# lan_board.net
KiCad netlist of a schematic drawn in Altium Designer
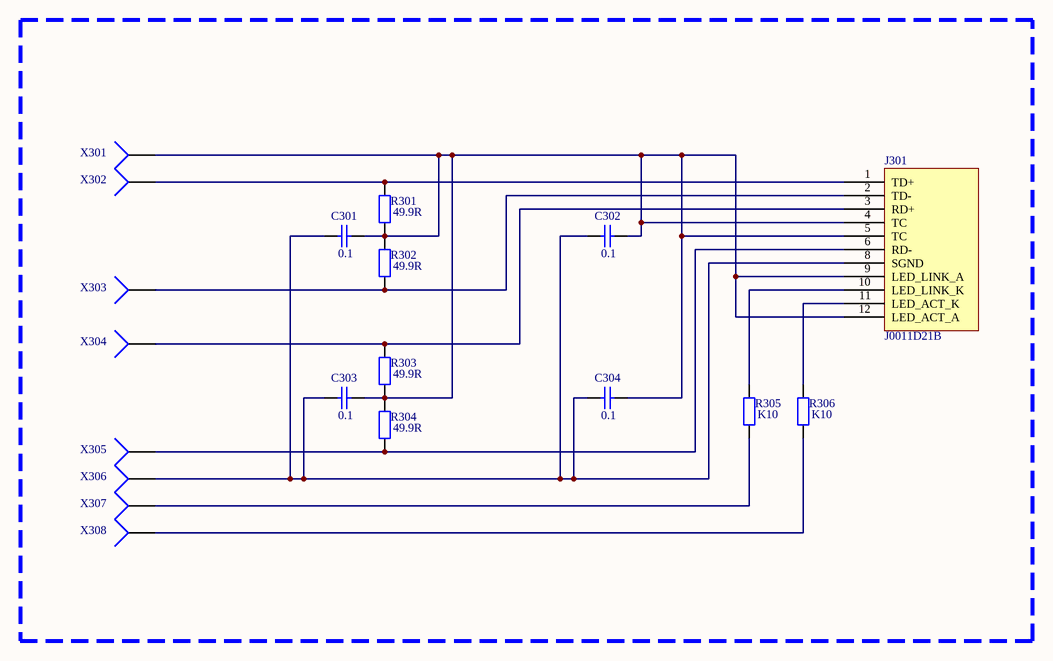
[diagram p0: lan_board.SchDoc]

(export (version "E")
  (design (tool "Eeschema 10.0.6"))
  (components
    (comp (ref "C301")
      (value "0.1")
      (footprint "C3216-1206")
      (description "Capacitor (Semiconductor SIM Model)")
      (fields (field (name "MANUFACTURER") "Generic Components") (field (name "PUBLISHER") "Altium Limited"))
      (libsource (lib "Miscellaneous Devices") (part "Cap Semi"))
    )
    (comp (ref "C302")
      (value "0.1")
      (footprint "C3216-1206")
      (description "Capacitor (Semiconductor SIM Model)")
      (fields (field (name "MANUFACTURER") "Generic Components") (field (name "PUBLISHER") "Altium Limited"))
      (libsource (lib "Miscellaneous Devices") (part "Cap Semi"))
    )
    (comp (ref "C303")
      (value "0.1")
      (footprint "C3216-1206")
      (description "Capacitor (Semiconductor SIM Model)")
      (fields (field (name "MANUFACTURER") "Generic Components") (field (name "PUBLISHER") "Altium Limited"))
      (libsource (lib "Miscellaneous Devices") (part "Cap Semi"))
    )
    (comp (ref "C304")
      (value "0.1")
      (footprint "C3216-1206")
      (description "Capacitor (Semiconductor SIM Model)")
      (fields (field (name "MANUFACTURER") "Generic Components") (field (name "PUBLISHER") "Altium Limited"))
      (libsource (lib "Miscellaneous Devices") (part "Cap Semi"))
    )
    (comp (ref "J301") (value "J0011D21B") (footprint "J0011D21B") (libsource (lib "PAL") (part "J0011D21B")))
    (comp (ref "R301")
      (value "49.9R")
      (footprint "_1206")
      (description "Resistor")
      (fields (field (name "MANUFACTURER") "Generic Components") (field (name "PUBLISHER") "Altium Limited"))
      (libsource (lib "Miscellaneous Devices") (part "Res2"))
    )
    (comp (ref "R302")
      (value "49.9R")
      (footprint "_1206")
      (description "Resistor")
      (fields (field (name "MANUFACTURER") "Generic Components") (field (name "PUBLISHER") "Altium Limited"))
      (libsource (lib "Miscellaneous Devices") (part "Res2"))
    )
    (comp (ref "R303")
      (value "49.9R")
      (footprint "_1206")
      (description "Resistor")
      (fields (field (name "MANUFACTURER") "Generic Components") (field (name "PUBLISHER") "Altium Limited"))
      (libsource (lib "Miscellaneous Devices") (part "Res2"))
    )
    (comp (ref "R304")
      (value "49.9R")
      (footprint "_1206")
      (description "Resistor")
      (fields (field (name "MANUFACTURER") "Generic Components") (field (name "PUBLISHER") "Altium Limited"))
      (libsource (lib "Miscellaneous Devices") (part "Res2"))
    )
    (comp (ref "R305")
      (value "K10")
      (footprint "_1206")
      (description "Resistor")
      (fields (field (name "MANUFACTURER") "Generic Components") (field (name "PUBLISHER") "Altium Limited"))
      (libsource (lib "Miscellaneous Devices") (part "Res2"))
    )
    (comp (ref "R306")
      (value "K10")
      (footprint "_1206")
      (description "Resistor")
      (fields (field (name "MANUFACTURER") "Generic Components") (field (name "PUBLISHER") "Altium Limited"))
      (libsource (lib "Miscellaneous Devices") (part "Res2"))
    )
    (comp (ref "X301")
      (value "~")
      (footprint "PIN1")
      (description "Socket")
      (fields (field (name "MANUFACTURER") "Generic Components") (field (name "PUBLISHER") "Altium Limited"))
      (libsource (lib "Miscellaneous Connectors") (part "Socket"))
    )
    (comp (ref "X302")
      (value "~")
      (footprint "PIN1")
      (description "Socket")
      (fields (field (name "MANUFACTURER") "Generic Components") (field (name "PUBLISHER") "Altium Limited"))
      (libsource (lib "Miscellaneous Connectors") (part "Socket"))
    )
    (comp (ref "X303")
      (value "~")
      (footprint "PIN1")
      (description "Socket")
      (fields (field (name "MANUFACTURER") "Generic Components") (field (name "PUBLISHER") "Altium Limited"))
      (libsource (lib "Miscellaneous Connectors") (part "Socket"))
    )
    (comp (ref "X304")
      (value "~")
      (footprint "PIN1")
      (description "Socket")
      (fields (field (name "MANUFACTURER") "Generic Components") (field (name "PUBLISHER") "Altium Limited"))
      (libsource (lib "Miscellaneous Connectors") (part "Socket"))
    )
    (comp (ref "X305")
      (value "~")
      (footprint "PIN1")
      (description "Socket")
      (fields (field (name "MANUFACTURER") "Generic Components") (field (name "PUBLISHER") "Altium Limited"))
      (libsource (lib "Miscellaneous Connectors") (part "Socket"))
    )
    (comp (ref "X306")
      (value "~")
      (footprint "PIN1")
      (description "Socket")
      (fields (field (name "MANUFACTURER") "Generic Components") (field (name "PUBLISHER") "Altium Limited"))
      (libsource (lib "Miscellaneous Connectors") (part "Socket"))
    )
    (comp (ref "X307")
      (value "~")
      (footprint "PIN1")
      (description "Socket")
      (fields (field (name "MANUFACTURER") "Generic Components") (field (name "PUBLISHER") "Altium Limited"))
      (libsource (lib "Miscellaneous Connectors") (part "Socket"))
    )
    (comp (ref "X308")
      (value "~")
      (footprint "PIN1")
      (description "Socket")
      (fields (field (name "MANUFACTURER") "Generic Components") (field (name "PUBLISHER") "Altium Limited"))
      (libsource (lib "Miscellaneous Connectors") (part "Socket"))
    )
  )
  (nets
    (net (code "1") (name "Net-(J301-LED_ACT_A)") (class "Default")
      (node (ref "C301") (pin "2") (pinfunction "2_2") (pintype "passive"))
      (node (ref "C302") (pin "2") (pinfunction "2_2") (pintype "passive"))
      (node (ref "C303") (pin "2") (pinfunction "2_2") (pintype "passive"))
      (node (ref "C304") (pin "2") (pinfunction "2_2") (pintype "passive"))
      (node (ref "J301") (pin "12") (pinfunction "LED_ACT_A_12") (pintype "passive"))
      (node (ref "J301") (pin "4") (pinfunction "TC_4") (pintype "passive"))
      (node (ref "J301") (pin "5") (pinfunction "TC_5") (pintype "passive"))
      (node (ref "J301") (pin "9") (pinfunction "LED_LINK_A_9") (pintype "passive"))
      (node (ref "R301") (pin "2") (pinfunction "2_2") (pintype "passive"))
      (node (ref "R302") (pin "1") (pinfunction "1_1") (pintype "passive"))
      (node (ref "R303") (pin "2") (pinfunction "2_2") (pintype "passive"))
      (node (ref "R304") (pin "1") (pinfunction "1_1") (pintype "passive"))
      (node (ref "X301") (pin "1") (pinfunction "1_1") (pintype "passive"))
    )
    (net (code "2") (name "Net-(J301-LED_ACT_K)") (class "Default")
      (node (ref "J301") (pin "11") (pinfunction "LED_ACT_K_11") (pintype "passive"))
      (node (ref "R306") (pin "1") (pinfunction "1_1") (pintype "passive"))
    )
    (net (code "3") (name "Net-(J301-LED_LINK_K)") (class "Default")
      (node (ref "J301") (pin "10") (pinfunction "LED_LINK_K_10") (pintype "passive"))
      (node (ref "R305") (pin "1") (pinfunction "1_1") (pintype "passive"))
    )
    (net (code "4") (name "Net-(J301-RD+)") (class "Default")
      (node (ref "J301") (pin "3") (pinfunction "RD+_3") (pintype "passive"))
      (node (ref "R303") (pin "1") (pinfunction "1_1") (pintype "passive"))
      (node (ref "X304") (pin "1") (pinfunction "1_1") (pintype "passive"))
    )
    (net (code "5") (name "Net-(J301-RD-)") (class "Default")
      (node (ref "J301") (pin "6") (pinfunction "RD-_6") (pintype "passive"))
      (node (ref "R304") (pin "2") (pinfunction "2_2") (pintype "passive"))
      (node (ref "X305") (pin "1") (pinfunction "1_1") (pintype "passive"))
    )
    (net (code "6") (name "Net-(J301-SGND)") (class "Default")
      (node (ref "C301") (pin "1") (pinfunction "1_1") (pintype "passive"))
      (node (ref "C302") (pin "1") (pinfunction "1_1") (pintype "passive"))
      (node (ref "C303") (pin "1") (pinfunction "1_1") (pintype "passive"))
      (node (ref "C304") (pin "1") (pinfunction "1_1") (pintype "passive"))
      (node (ref "J301") (pin "8") (pinfunction "SGND_8") (pintype "passive"))
      (node (ref "X306") (pin "1") (pinfunction "1_1") (pintype "passive"))
    )
    (net (code "7") (name "Net-(J301-TD+)") (class "Default")
      (node (ref "J301") (pin "1") (pinfunction "TD+_1") (pintype "passive"))
      (node (ref "R301") (pin "1") (pinfunction "1_1") (pintype "passive"))
      (node (ref "X302") (pin "1") (pinfunction "1_1") (pintype "passive"))
    )
    (net (code "8") (name "Net-(J301-TD-)") (class "Default")
      (node (ref "J301") (pin "2") (pinfunction "TD-_2") (pintype "passive"))
      (node (ref "R302") (pin "2") (pinfunction "2_2") (pintype "passive"))
      (node (ref "X303") (pin "1") (pinfunction "1_1") (pintype "passive"))
    )
    (net (code "9") (name "Net-(R305-Pad2)") (class "Default")
      (node (ref "R305") (pin "2") (pinfunction "2_2") (pintype "passive"))
      (node (ref "X307") (pin "1") (pinfunction "1_1") (pintype "passive"))
    )
    (net (code "10") (name "Net-(R306-Pad2)") (class "Default")
      (node (ref "R306") (pin "2") (pinfunction "2_2") (pintype "passive"))
      (node (ref "X308") (pin "1") (pinfunction "1_1") (pintype "passive"))
    )
  )
)
